# schematic_final.net
KiCad netlist of a schematic drawn in EAGLE
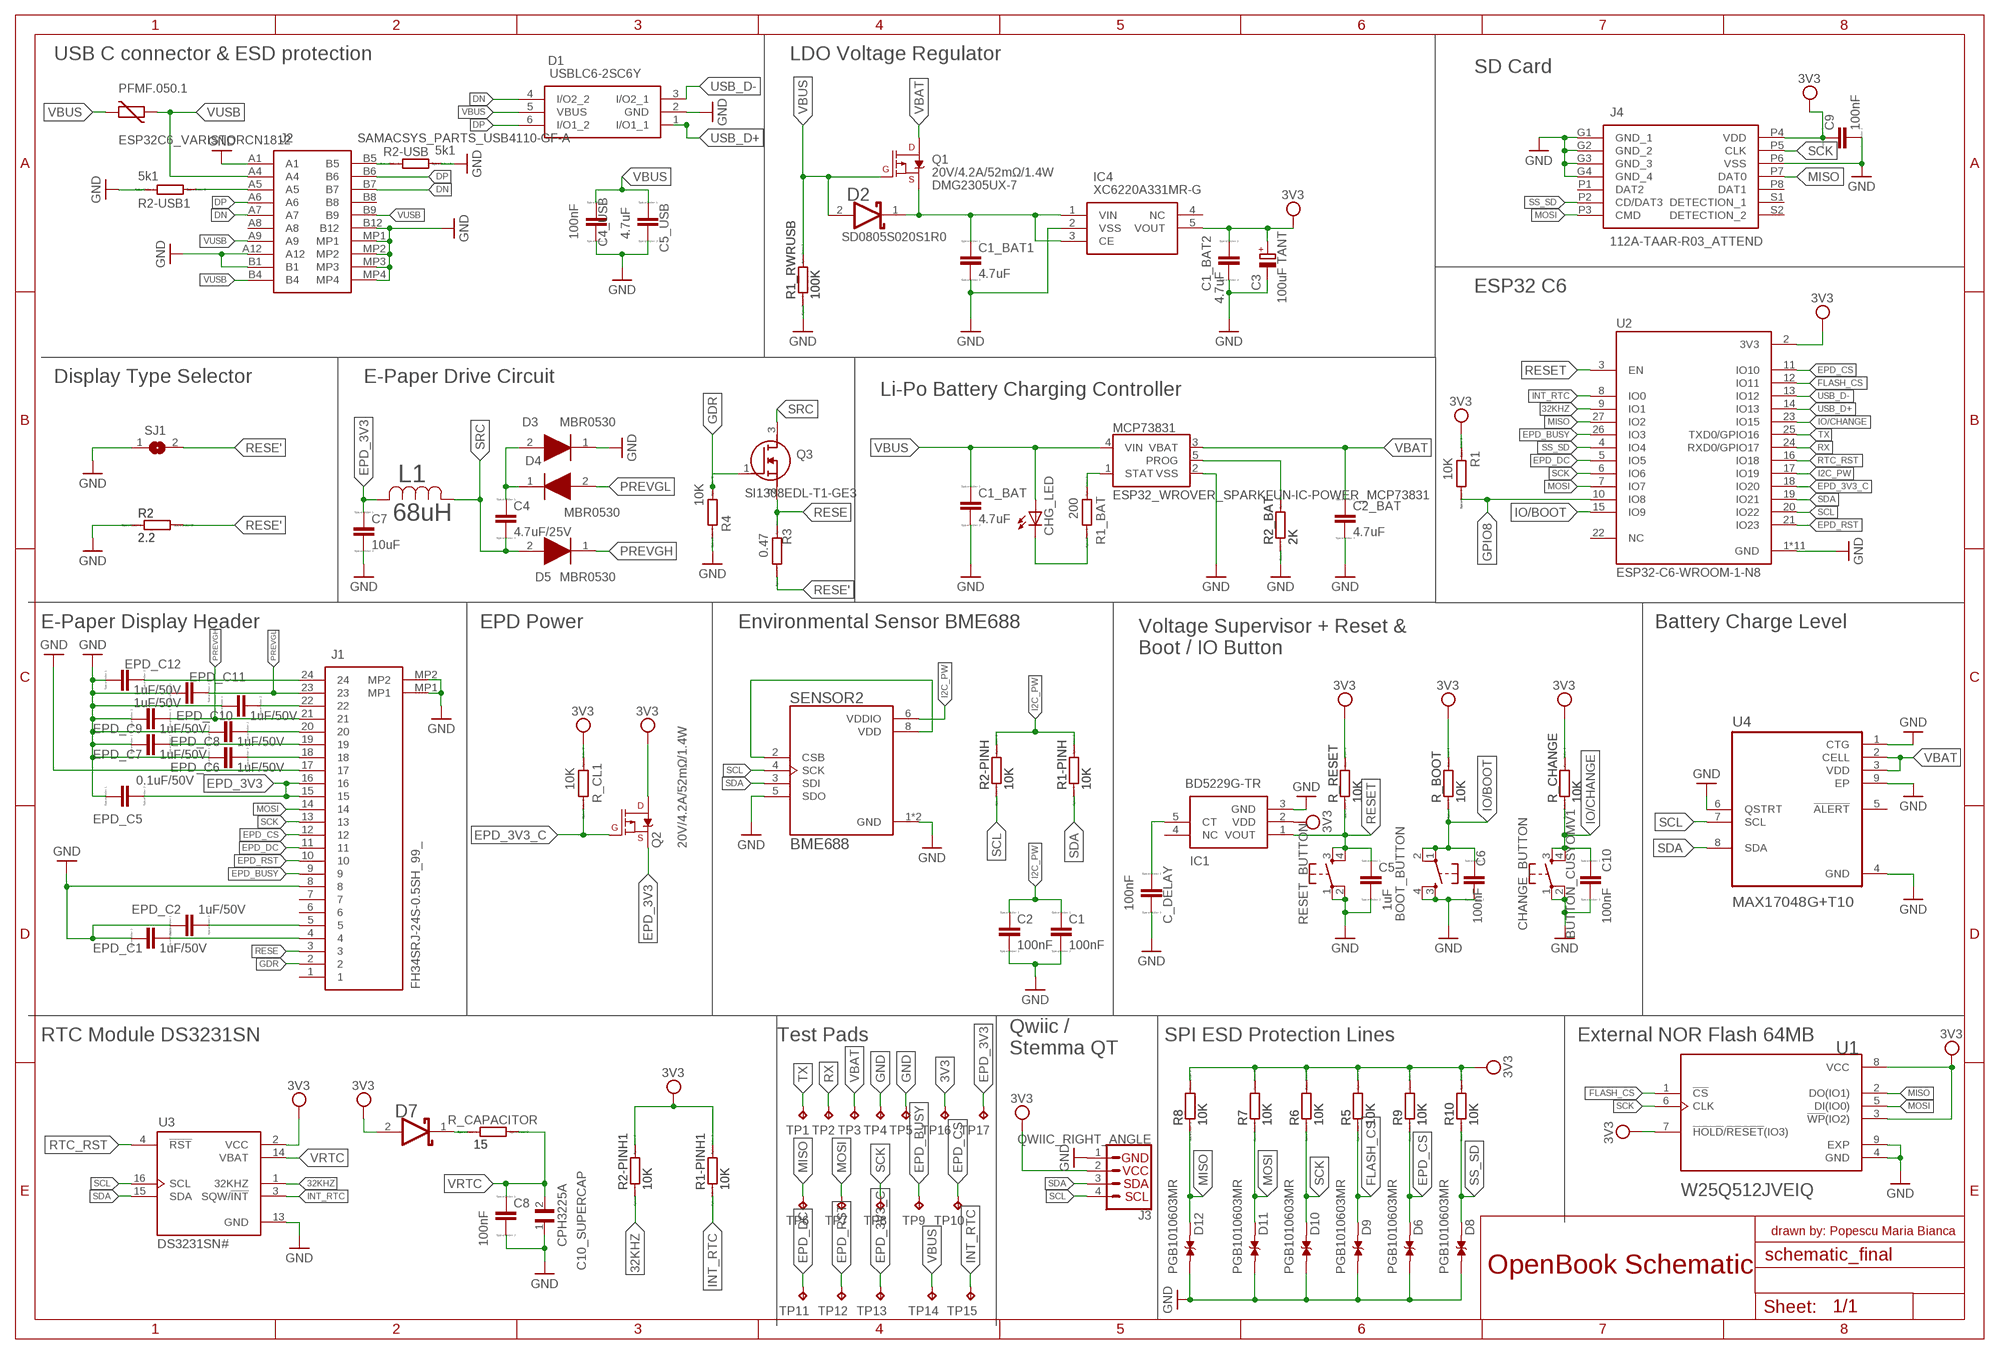
[diagram p0: schematic, sheet 1]

(export (version "E")
  (design (tool "Eeschema 10.0.6"))
  (components
    (comp (ref "BOOT_BUTTON")
      (value "BUTTON_CUSYOMV1")
      (footprint "eagle-import:MYBUTTON")
      (libsource (lib "eagle-import") (part "BUTTON_CUSYOMV1"))
    )
    (comp (ref "C1")
      (value "100nF")
      (footprint "eagle-import:EAGLE-LTSPICE_C0402")
      (libsource (lib "eagle-import") (part "EAGLE-LTSPICE_CC0402"))
    )
    (comp (ref "C1_BAT")
      (value "4.7uF")
      (footprint "eagle-import:EAGLE-LTSPICE_C0402")
      (libsource (lib "eagle-import") (part "EAGLE-LTSPICE_CC0402"))
    )
    (comp (ref "C1_BAT1")
      (value "4.7uF")
      (footprint "eagle-import:EAGLE-LTSPICE_C0402")
      (libsource (lib "eagle-import") (part "EAGLE-LTSPICE_CC0402"))
    )
    (comp (ref "C1_BAT2")
      (value "4.7uF")
      (footprint "eagle-import:EAGLE-LTSPICE_C0402")
      (libsource (lib "eagle-import") (part "EAGLE-LTSPICE_CC0402"))
    )
    (comp (ref "C2")
      (value "100nF")
      (footprint "eagle-import:EAGLE-LTSPICE_C0402")
      (libsource (lib "eagle-import") (part "EAGLE-LTSPICE_CC0402"))
    )
    (comp (ref "C2_BAT")
      (value "4.7uF")
      (footprint "eagle-import:EAGLE-LTSPICE_C0402")
      (libsource (lib "eagle-import") (part "EAGLE-LTSPICE_CC0402"))
    )
    (comp (ref "C3")
      (value "100uF TANT")
      (footprint "eagle-import:RCL_CT3528")
      (libsource (lib "eagle-import") (part "RCL_CPOL-EUCT3528"))
    )
    (comp (ref "C4")
      (value "4.7uF/25V")
      (footprint "eagle-import:EAGLE-LTSPICE_C0402")
      (libsource (lib "eagle-import") (part "EAGLE-LTSPICE_CC0402"))
    )
    (comp (ref "C4_USB")
      (value "100nF")
      (footprint "eagle-import:EAGLE-LTSPICE_C0402")
      (libsource (lib "eagle-import") (part "EAGLE-LTSPICE_CC0402"))
    )
    (comp (ref "C5")
      (value "1uF")
      (footprint "eagle-import:EAGLE-LTSPICE_C0402")
      (libsource (lib "eagle-import") (part "EAGLE-LTSPICE_CC0402"))
    )
    (comp (ref "C5_USB")
      (value "4.7uF")
      (footprint "eagle-import:EAGLE-LTSPICE_C0402")
      (libsource (lib "eagle-import") (part "EAGLE-LTSPICE_CC0402"))
    )
    (comp (ref "C6")
      (value "100nF")
      (footprint "eagle-import:EAGLE-LTSPICE_C0402")
      (libsource (lib "eagle-import") (part "EAGLE-LTSPICE_CC0402"))
    )
    (comp (ref "C7")
      (value "10uF")
      (footprint "eagle-import:EAGLE-LTSPICE_C0402")
      (libsource (lib "eagle-import") (part "EAGLE-LTSPICE_CC0402"))
    )
    (comp (ref "C8")
      (value "100nF")
      (footprint "eagle-import:EAGLE-LTSPICE_C0402")
      (libsource (lib "eagle-import") (part "EAGLE-LTSPICE_CC0402"))
    )
    (comp (ref "C9")
      (value "100nF")
      (footprint "eagle-import:EAGLE-LTSPICE_C0402")
      (libsource (lib "eagle-import") (part "EAGLE-LTSPICE_CC0402"))
    )
    (comp (ref "C10")
      (value "100nF")
      (footprint "eagle-import:EAGLE-LTSPICE_C0402")
      (libsource (lib "eagle-import") (part "EAGLE-LTSPICE_CC0402"))
    )
    (comp (ref "C10_SUPERCAP")
      (value "CPH3225A")
      (footprint "eagle-import:CAPCP3225X100N")
      (fields (field (name "MF") "Seiko Instruments"))
      (libsource (lib "eagle-import") (part "CPH3225A"))
    )
    (comp (ref "CHANGE_BUTTON")
      (value "BUTTON_CUSYOMV1")
      (footprint "eagle-import:MYBUTTON")
      (libsource (lib "eagle-import") (part "BUTTON_CUSYOMV1"))
    )
    (comp (ref "CHG_LED")
      (value "ADAFRUIT_LEDCHIP-LED0603")
      (footprint "eagle-import:ADAFRUIT_CHIP-LED0603")
      (libsource (lib "eagle-import") (part "ADAFRUIT_LEDCHIP-LED0603"))
    )
    (comp (ref "C_DELAY")
      (value "100nF")
      (footprint "eagle-import:EAGLE-LTSPICE_C0402")
      (libsource (lib "eagle-import") (part "EAGLE-LTSPICE_CC0402"))
    )
    (comp (ref "D1")
      (value "USBLC6-2SC6Y")
      (footprint "eagle-import:SOT95P280X145-6N")
      (fields (field (name "MF") "STMicroelectronics"))
      (libsource (lib "eagle-import") (part "USBLC6-2SC6Y"))
    )
    (comp (ref "D2")
      (value "SD0805S020S1R0")
      (footprint "eagle-import:ESP32_WROVER_AVX---SD0805S020S1R0_AVX_SD0805S020S1R0_0")
      (fields
        (field (name "DIGIKEY_PART_NUMBER") "478-7800-1-ND")
        (field (name "MF") "AVX")
        (field (name "MOUSER_PART_NUMBER") "581-SD0805S020S1R0")
        (field (name "ATTR") "SD0805S020S1R0")
      )
      (libsource (lib "eagle-import") (part "ESP32_WROVER_AVX---SD0805S020S1R0_AVX_SD0805S020S1R0_0_0AVX_SD0805S020S1R0_0_0"))
    )
    (comp (ref "D3")
      (value "MBR0530")
      (footprint "eagle-import:SOD3716X135N")
      (fields (field (name "MF") "ON Semiconductor"))
      (libsource (lib "eagle-import") (part "MBR0530"))
    )
    (comp (ref "D4")
      (value "MBR0530")
      (footprint "eagle-import:SOD3716X135N")
      (fields (field (name "MF") "ON Semiconductor"))
      (libsource (lib "eagle-import") (part "MBR0530"))
    )
    (comp (ref "D5")
      (value "MBR0530")
      (footprint "eagle-import:SOD3716X135N")
      (fields (field (name "MF") "ON Semiconductor"))
      (libsource (lib "eagle-import") (part "MBR0530"))
    )
    (comp (ref "D6")
      (value "PGB1010603MR")
      (footprint "eagle-import:DIOC1608X36N")
      (fields (field (name "MF") "Littelfuse Inc."))
      (libsource (lib "eagle-import") (part "PGB1010603MR"))
    )
    (comp (ref "D7")
      (value "ESP32_WROVER_AVX---SD0805S020S1R0_AVX_SD0805S020S1R0_0_0AVX_SD0805S020S1R0_0_0")
      (footprint "eagle-import:ESP32_WROVER_AVX---SD0805S020S1R0_AVX_SD0805S020S1R0_0")
      (fields
        (field (name "DIGIKEY_PART_NUMBER") "478-7800-1-ND")
        (field (name "MF") "AVX")
        (field (name "MOUSER_PART_NUMBER") "581-SD0805S020S1R0")
      )
      (libsource (lib "eagle-import") (part "ESP32_WROVER_AVX---SD0805S020S1R0_AVX_SD0805S020S1R0_0_0AVX_SD0805S020S1R0_0_0"))
    )
    (comp (ref "D8")
      (value "PGB1010603MR")
      (footprint "eagle-import:DIOC1608X36N")
      (fields (field (name "MF") "Littelfuse Inc."))
      (libsource (lib "eagle-import") (part "PGB1010603MR"))
    )
    (comp (ref "D9")
      (value "PGB1010603MR")
      (footprint "eagle-import:DIOC1608X36N")
      (fields (field (name "MF") "Littelfuse Inc."))
      (libsource (lib "eagle-import") (part "PGB1010603MR"))
    )
    (comp (ref "D10")
      (value "PGB1010603MR")
      (footprint "eagle-import:DIOC1608X36N")
      (fields (field (name "MF") "Littelfuse Inc."))
      (libsource (lib "eagle-import") (part "PGB1010603MR"))
    )
    (comp (ref "D11")
      (value "PGB1010603MR")
      (footprint "eagle-import:DIOC1608X36N")
      (fields (field (name "MF") "Littelfuse Inc."))
      (libsource (lib "eagle-import") (part "PGB1010603MR"))
    )
    (comp (ref "D12")
      (value "PGB1010603MR")
      (footprint "eagle-import:DIOC1608X36N")
      (fields (field (name "MF") "Littelfuse Inc."))
      (libsource (lib "eagle-import") (part "PGB1010603MR"))
    )
    (comp (ref "EPD_C1")
      (value "1uF/50V")
      (footprint "eagle-import:EAGLE-LTSPICE_C0402")
      (libsource (lib "eagle-import") (part "EAGLE-LTSPICE_CC0402"))
    )
    (comp (ref "EPD_C2")
      (value "1uF/50V")
      (footprint "eagle-import:EAGLE-LTSPICE_C0402")
      (libsource (lib "eagle-import") (part "EAGLE-LTSPICE_CC0402"))
    )
    (comp (ref "EPD_C5")
      (value "0.1uF/50V")
      (footprint "eagle-import:EAGLE-LTSPICE_C0402")
      (libsource (lib "eagle-import") (part "EAGLE-LTSPICE_CC0402"))
    )
    (comp (ref "EPD_C6")
      (value "1uF/50V")
      (footprint "eagle-import:EAGLE-LTSPICE_C0402")
      (libsource (lib "eagle-import") (part "EAGLE-LTSPICE_CC0402"))
    )
    (comp (ref "EPD_C7")
      (value "1uF/50V")
      (footprint "eagle-import:EAGLE-LTSPICE_C0402")
      (libsource (lib "eagle-import") (part "EAGLE-LTSPICE_CC0402"))
    )
    (comp (ref "EPD_C8")
      (value "1uF/50V")
      (footprint "eagle-import:EAGLE-LTSPICE_C0402")
      (libsource (lib "eagle-import") (part "EAGLE-LTSPICE_CC0402"))
    )
    (comp (ref "EPD_C9")
      (value "1uF/50V")
      (footprint "eagle-import:EAGLE-LTSPICE_C0402")
      (libsource (lib "eagle-import") (part "EAGLE-LTSPICE_CC0402"))
    )
    (comp (ref "EPD_C10")
      (value "1uF/50V")
      (footprint "eagle-import:EAGLE-LTSPICE_C0402")
      (libsource (lib "eagle-import") (part "EAGLE-LTSPICE_CC0402"))
    )
    (comp (ref "EPD_C11")
      (value "1uF/50V")
      (footprint "eagle-import:EAGLE-LTSPICE_C0402")
      (libsource (lib "eagle-import") (part "EAGLE-LTSPICE_CC0402"))
    )
    (comp (ref "EPD_C12")
      (value "1uF/50V")
      (footprint "eagle-import:EAGLE-LTSPICE_C0402")
      (libsource (lib "eagle-import") (part "EAGLE-LTSPICE_CC0402"))
    )
    (comp (ref "IC1")
      (value "BD5229G-TR")
      (footprint "eagle-import:SOT95P280X125-5N")
      (fields (field (name "MOUSER_PART_NUMBER") "755-BD5229G-TR"))
      (libsource (lib "eagle-import") (part "BD5229G-TR"))
    )
    (comp (ref "IC4")
      (value "XC6220A331MR-G")
      (footprint "eagle-import:SOT95P280X120-5N")
      (fields (field (name "MOUSER_PART_NUMBER") "865-XC6220A331MR-G"))
      (libsource (lib "eagle-import") (part "XC6220A331MR-G"))
    )
    (comp (ref "J1")
      (value "FH34SRJ-24S-0.5SH_99_")
      (footprint "eagle-import:FH34SRJ24S05SH99")
      (fields
        (field (name "MANUFACTURER_PART_NUMBER") "FH34SRJ-24S-0.5SH(99)")
        (field (name "MOUSER_PART_NUMBER") "798-FH34SRJ24S05SH99")
      )
      (libsource (lib "eagle-import") (part "FH34SRJ-24S-0.5SH_99_"))
    )
    (comp (ref "J2")
      (value "SAMACSYS_PARTS_USB4110-GF-A")
      (footprint "eagle-import:SAMACSYS_PARTS_USB4110GFA")
      (fields
        (field (name "MANUFACTURER_PART_NUMBER") "USB4110-GF-A")
        (field (name "MOUSER_PART_NUMBER") "640-USB4110-GF-A")
      )
      (libsource (lib "eagle-import") (part "SAMACSYS_PARTS_USB4110-GF-A"))
    )
    (comp (ref "J3")
      (value "QWIIC_RIGHT_ANGLE")
      (footprint "eagle-import:JST04_1MM_RA")
      (libsource (lib "eagle-import") (part "QWIIC_CONNECTORJS-1MM"))
    )
    (comp (ref "J4")
      (value "112A-TAAR-R03_ATTEND")
      (footprint "eagle-import:112ATAARR03ATTEND")
      (fields (field (name "MANUFACTURER_PART_NUMBER") "112A-TAAR-R03 ATTEND"))
      (libsource (lib "eagle-import") (part "112A-TAAR-R03_ATTEND"))
    )
    (comp (ref "L1")
      (value "68uH")
      (footprint "eagle-import:IND_4828-WE-TPC_WRE")
      (fields
        (field (name "MANUFACTURER_PART_NUMBER") "744043680")
        (field (name "COPYRIGHT") "Copyright (C) 2024 Ultra Librarian. All rights reserved.")
      )
      (libsource (lib "eagle-import") (part "744043680IND_4828-WE-TPC_WRE"))
    )
    (comp (ref "MCP73831")
      (value "ESP32_WROVER_SPARKFUN-IC-POWER_MCP73831")
      (footprint "eagle-import:ESP32_WROVER_SPARKFUN-IC-POWER_SOT23-5")
      (libsource (lib "eagle-import") (part "ESP32_WROVER_SPARKFUN-IC-POWER_MCP73831"))
    )
    (comp (ref "PFMF.050.1")
      (value "ESP32C6_VARISTORCN1812")
      (footprint "eagle-import:ESP32C6_VARISTOR_CT_CN1812")
      (libsource (lib "eagle-import") (part "ESP32C6_VARISTORCN1812"))
    )
    (comp (ref "Q1")
      (value "20V/4.2A/52mΩ/1.4W")
      (footprint "eagle-import:ESP32_WROVER_SPARKFUN-DISCRETESEMI_SOT23-3")
      (fields (field (name "ATTR") "DMG2305UX-7"))
      (libsource (lib "eagle-import") (part "ESP32_WROVER_SPARKFUN-DISCRETESEMI_MOSFET_PCH-DMG2305UX-7"))
    )
    (comp (ref "Q2")
      (value "20V/4.2A/52mΩ/1.4W")
      (footprint "eagle-import:ESP32_WROVER_SPARKFUN-DISCRETESEMI_SOT23-3")
      (libsource (lib "eagle-import") (part "ESP32_WROVER_SPARKFUN-DISCRETESEMI_MOSFET_PCH-DMG2305UX-7"))
    )
    (comp (ref "Q3")
      (value "SI1308EDL-T1-GE3")
      (footprint "eagle-import:SOT65P210X110-3N")
      (fields (field (name "MF") "Vishay Siliconix"))
      (libsource (lib "eagle-import") (part "SI1308EDL-T1-GE3"))
    )
    (comp (ref "R1")
      (value "10K")
      (footprint "eagle-import:ESP32_WROVER_EAGLE-LTSPICE_R0402")
      (libsource (lib "eagle-import") (part "ESP32_WROVER_EAGLE-LTSPICE_RR0402"))
    )
    (comp (ref "R1-PINH")
      (value "10K")
      (footprint "eagle-import:ESP32_WROVER_EAGLE-LTSPICE_R0402")
      (libsource (lib "eagle-import") (part "ESP32_WROVER_EAGLE-LTSPICE_RR0402"))
    )
    (comp (ref "R1-PINH1")
      (value "10K")
      (footprint "eagle-import:ESP32_WROVER_EAGLE-LTSPICE_R0402")
      (libsource (lib "eagle-import") (part "ESP32_WROVER_EAGLE-LTSPICE_RR0402"))
    )
    (comp (ref "R1_BAT")
      (value "200")
      (footprint "eagle-import:ESP32_WROVER_EAGLE-LTSPICE_R0402")
      (libsource (lib "eagle-import") (part "ESP32_WROVER_EAGLE-LTSPICE_RR0402"))
    )
    (comp (ref "R1_RWRUSB")
      (value "100K")
      (footprint "eagle-import:ESP32_WROVER_EAGLE-LTSPICE_R0402")
      (libsource (lib "eagle-import") (part "ESP32_WROVER_EAGLE-LTSPICE_RR0402"))
    )
    (comp (ref "R2")
      (value "2.2")
      (footprint "eagle-import:ESP32_WROVER_EAGLE-LTSPICE_R0402")
      (libsource (lib "eagle-import") (part "ESP32_WROVER_EAGLE-LTSPICE_RR0402"))
    )
    (comp (ref "R2-PINH")
      (value "10K")
      (footprint "eagle-import:ESP32_WROVER_EAGLE-LTSPICE_R0402")
      (libsource (lib "eagle-import") (part "ESP32_WROVER_EAGLE-LTSPICE_RR0402"))
    )
    (comp (ref "R2-PINH1")
      (value "10K")
      (footprint "eagle-import:ESP32_WROVER_EAGLE-LTSPICE_R0402")
      (libsource (lib "eagle-import") (part "ESP32_WROVER_EAGLE-LTSPICE_RR0402"))
    )
    (comp (ref "R2-USB")
      (value "5k1")
      (footprint "eagle-import:ESP32_WROVER_EAGLE-LTSPICE_R0402")
      (libsource (lib "eagle-import") (part "ESP32_WROVER_EAGLE-LTSPICE_RR0402"))
    )
    (comp (ref "R2-USB1")
      (value "5k1")
      (footprint "eagle-import:ESP32_WROVER_EAGLE-LTSPICE_R0402")
      (libsource (lib "eagle-import") (part "ESP32_WROVER_EAGLE-LTSPICE_RR0402"))
    )
    (comp (ref "R2_BAT")
      (value "2K")
      (footprint "eagle-import:ESP32_WROVER_EAGLE-LTSPICE_R0402")
      (libsource (lib "eagle-import") (part "ESP32_WROVER_EAGLE-LTSPICE_RR0402"))
    )
    (comp (ref "R3")
      (value "0.47")
      (footprint "eagle-import:ESP32_WROVER_EAGLE-LTSPICE_R0402")
      (libsource (lib "eagle-import") (part "ESP32_WROVER_EAGLE-LTSPICE_RR0402"))
    )
    (comp (ref "R4")
      (value "10K")
      (footprint "eagle-import:ESP32_WROVER_EAGLE-LTSPICE_R0402")
      (libsource (lib "eagle-import") (part "ESP32_WROVER_EAGLE-LTSPICE_RR0402"))
    )
    (comp (ref "R5")
      (value "10K")
      (footprint "eagle-import:ESP32_WROVER_EAGLE-LTSPICE_R0402")
      (libsource (lib "eagle-import") (part "ESP32_WROVER_EAGLE-LTSPICE_RR0402"))
    )
    (comp (ref "R6")
      (value "10K")
      (footprint "eagle-import:ESP32_WROVER_EAGLE-LTSPICE_R0402")
      (libsource (lib "eagle-import") (part "ESP32_WROVER_EAGLE-LTSPICE_RR0402"))
    )
    (comp (ref "R7")
      (value "10K")
      (footprint "eagle-import:ESP32_WROVER_EAGLE-LTSPICE_R0402")
      (libsource (lib "eagle-import") (part "ESP32_WROVER_EAGLE-LTSPICE_RR0402"))
    )
    (comp (ref "R8")
      (value "10K")
      (footprint "eagle-import:ESP32_WROVER_EAGLE-LTSPICE_R0402")
      (libsource (lib "eagle-import") (part "ESP32_WROVER_EAGLE-LTSPICE_RR0402"))
    )
    (comp (ref "R9")
      (value "10K")
      (footprint "eagle-import:ESP32_WROVER_EAGLE-LTSPICE_R0402")
      (libsource (lib "eagle-import") (part "ESP32_WROVER_EAGLE-LTSPICE_RR0402"))
    )
    (comp (ref "R10")
      (value "10K")
      (footprint "eagle-import:ESP32_WROVER_EAGLE-LTSPICE_R0402")
      (libsource (lib "eagle-import") (part "ESP32_WROVER_EAGLE-LTSPICE_RR0402"))
    )
    (comp (ref "RESET_BUTTON")
      (value "RESET_BUTTON")
      (footprint "eagle-import:MYBUTTON")
      (libsource (lib "eagle-import") (part "BUTTON_CUSYOMV1"))
    )
    (comp (ref "R_BOOT")
      (value "10K")
      (footprint "eagle-import:ESP32_WROVER_EAGLE-LTSPICE_R0402")
      (libsource (lib "eagle-import") (part "ESP32_WROVER_EAGLE-LTSPICE_RR0402"))
    )
    (comp (ref "R_CAPACITOR")
      (value "15")
      (footprint "eagle-import:ESP32_WROVER_EAGLE-LTSPICE_R0402")
      (libsource (lib "eagle-import") (part "ESP32_WROVER_EAGLE-LTSPICE_RR0402"))
    )
    (comp (ref "R_CHANGE")
      (value "10K")
      (footprint "eagle-import:ESP32_WROVER_EAGLE-LTSPICE_R0402")
      (libsource (lib "eagle-import") (part "ESP32_WROVER_EAGLE-LTSPICE_RR0402"))
    )
    (comp (ref "R_CL1")
      (value "10K")
      (footprint "eagle-import:ESP32_WROVER_EAGLE-LTSPICE_R0402")
      (libsource (lib "eagle-import") (part "ESP32_WROVER_EAGLE-LTSPICE_RR0402"))
    )
    (comp (ref "R_RESET")
      (value "10K")
      (footprint "eagle-import:ESP32_WROVER_EAGLE-LTSPICE_R0402")
      (libsource (lib "eagle-import") (part "ESP32_WROVER_EAGLE-LTSPICE_RR0402"))
    )
    (comp (ref "SENSOR2")
      (value "BME688")
      (footprint "eagle-import:ESP32_WROVER_BME680_PSON80P300X300X100-8N")
      (fields (field (name "MF") "Bosch Sensortec") (field (name "MP") "BME680"))
      (libsource (lib "eagle-import") (part "ESP32_WROVER_BME680_BME680"))
    )
    (comp (ref "SJ1") (value "SJ") (footprint "eagle-import:SJ") (libsource (lib "eagle-import") (part "SJ")))
    (comp (ref "TP1")
      (value "TPTP20R")
      (footprint "eagle-import:TP20R")
      (libsource (lib "eagle-import") (part "TPTP20R"))
    )
    (comp (ref "TP2")
      (value "TPTP20R")
      (footprint "eagle-import:TP20R")
      (libsource (lib "eagle-import") (part "TPTP20R"))
    )
    (comp (ref "TP3")
      (value "TPTP20R")
      (footprint "eagle-import:TP20R")
      (libsource (lib "eagle-import") (part "TPTP20R"))
    )
    (comp (ref "TP4")
      (value "TPTP20R")
      (footprint "eagle-import:TP20R")
      (libsource (lib "eagle-import") (part "TPTP20R"))
    )
    (comp (ref "TP5")
      (value "TPTP20R")
      (footprint "eagle-import:TP20R")
      (libsource (lib "eagle-import") (part "TPTP20R"))
    )
    (comp (ref "TP6")
      (value "TPTP20R")
      (footprint "eagle-import:TP20R")
      (libsource (lib "eagle-import") (part "TPTP20R"))
    )
    (comp (ref "TP7")
      (value "TPTP20R")
      (footprint "eagle-import:TP20R")
      (libsource (lib "eagle-import") (part "TPTP20R"))
    )
    (comp (ref "TP8")
      (value "TPTP20R")
      (footprint "eagle-import:TP20R")
      (libsource (lib "eagle-import") (part "TPTP20R"))
    )
    (comp (ref "TP9")
      (value "TPTP20R")
      (footprint "eagle-import:TP20R")
      (libsource (lib "eagle-import") (part "TPTP20R"))
    )
    (comp (ref "TP10")
      (value "TPTP20R")
      (footprint "eagle-import:TP20R")
      (libsource (lib "eagle-import") (part "TPTP20R"))
    )
    (comp (ref "TP11")
      (value "TPTP20R")
      (footprint "eagle-import:TP20R")
      (libsource (lib "eagle-import") (part "TPTP20R"))
    )
    (comp (ref "TP12")
      (value "TPTP20R")
      (footprint "eagle-import:TP20R")
      (libsource (lib "eagle-import") (part "TPTP20R"))
    )
    (comp (ref "TP13")
      (value "TPTP20R")
      (footprint "eagle-import:TP20R")
      (libsource (lib "eagle-import") (part "TPTP20R"))
    )
    (comp (ref "TP14")
      (value "TPTP20R")
      (footprint "eagle-import:TP20R")
      (libsource (lib "eagle-import") (part "TPTP20R"))
    )
    (comp (ref "TP15")
      (value "TPTP20R")
      (footprint "eagle-import:TP20R")
      (libsource (lib "eagle-import") (part "TPTP20R"))
    )
    (comp (ref "TP16")
      (value "TPTP20R")
      (footprint "eagle-import:TP20R")
      (libsource (lib "eagle-import") (part "TPTP20R"))
    )
    (comp (ref "TP17")
      (value "TPTP20R")
      (footprint "eagle-import:TP20R")
      (libsource (lib "eagle-import") (part "TPTP20R"))
    )
    (comp (ref "U1")
      (value "W25Q512JVEIQ")
      (footprint "eagle-import:SON127P600X800X80-9N")
      (fields (field (name "MF") "Winbond Electronics"))
      (libsource (lib "eagle-import") (part "W25Q512JVEIQ"))
    )
    (comp (ref "U2")
      (value "ESP32-C6-WROOM-1-N8")
      (footprint "eagle-import:XCVR_ESP32-C6-WROOM-1-N8")
      (fields (field (name "MF") "Espressif Systems"))
      (libsource (lib "eagle-import") (part "ESP32-C6-WROOM-1-N8"))
    )
    (comp (ref "U3")
      (value "DS3231SN#")
      (footprint "eagle-import:SOIC127P1032X265-16N")
      (fields (field (name "MF") "Analog Devices"))
      (libsource (lib "eagle-import") (part "DS3231SN#"))
    )
    (comp (ref "U4")
      (value "MAX17048G+T10")
      (footprint "eagle-import:SON50P200X200X80-9N")
      (fields (field (name "MF") "Analog Devices"))
      (libsource (lib "eagle-import") (part "MAX17048G+T10"))
    )
  )
  (nets
    (net (code "1") (name "3V3") (class "Default")
      (node (ref "C1_BAT2") (pin "1") (pinfunction "1_1") (pintype "passive"))
      (node (ref "C3") (pin "+") (pinfunction "+_+") (pintype "passive"))
      (node (ref "C9") (pin "1") (pinfunction "1_1") (pintype "passive"))
      (node (ref "D7") (pin "2") (pinfunction "ANODE_2") (pintype "bidirectional"))
      (node (ref "IC1") (pin "2") (pinfunction "VDD_2") (pintype "bidirectional"))
      (node (ref "IC4") (pin "5") (pinfunction "VOUT_5") (pintype "bidirectional"))
      (node (ref "J3") (pin "2") (pinfunction "2_2") (pintype "power_in"))
      (node (ref "J4") (pin "P4") (pinfunction "VDD_P4") (pintype "bidirectional"))
      (node (ref "Q2") (pin "3") (pinfunction "D_3") (pintype "bidirectional"))
      (node (ref "R1") (pin "2") (pinfunction "2_2") (pintype "passive"))
      (node (ref "R1-PINH1") (pin "2") (pinfunction "2_2") (pintype "passive"))
      (node (ref "R10") (pin "2") (pinfunction "2_2") (pintype "passive"))
      (node (ref "R2-PINH1") (pin "2") (pinfunction "2_2") (pintype "passive"))
      (node (ref "R5") (pin "2") (pinfunction "2_2") (pintype "passive"))
      (node (ref "R6") (pin "2") (pinfunction "2_2") (pintype "passive"))
      (node (ref "R7") (pin "2") (pinfunction "2_2") (pintype "passive"))
      (node (ref "R8") (pin "2") (pinfunction "2_2") (pintype "passive"))
      (node (ref "R9") (pin "2") (pinfunction "2_2") (pintype "passive"))
      (node (ref "R_BOOT") (pin "2") (pinfunction "2_2") (pintype "passive"))
      (node (ref "R_CHANGE") (pin "2") (pinfunction "2_2") (pintype "passive"))
      (node (ref "R_CL1") (pin "2") (pinfunction "2_2") (pintype "passive"))
      (node (ref "R_RESET") (pin "2") (pinfunction "2_2") (pintype "passive"))
      (node (ref "TP16") (pin "TP") (pinfunction "TP_TP") (pintype "input"))
      (node (ref "U1") (pin "3") (pinfunction "~{WP}(IO2)_3") (pintype "bidirectional"))
      (node (ref "U1") (pin "7") (pinfunction "~{HOLD}/~{RESET}(IO3)_7") (pintype "bidirectional"))
      (node (ref "U1") (pin "8") (pinfunction "VCC_8") (pintype "power_in"))
      (node (ref "U2") (pin "2") (pinfunction "3V3_2") (pintype "power_in"))
      (node (ref "U3") (pin "2") (pinfunction "VCC_2") (pintype "power_in"))
    )
    (net (code "2") (name "32KHZ") (class "Default")
      (node (ref "R2-PINH1") (pin "1") (pinfunction "1_1") (pintype "passive"))
      (node (ref "U2") (pin "9") (pinfunction "IO1_9") (pintype "bidirectional"))
      (node (ref "U3") (pin "1") (pinfunction "32KHZ_1") (pintype "output"))
    )
    (net (code "3") (name "DN") (class "Default")
      (node (ref "D1") (pin "4") (pinfunction "I/O2_2_4") (pintype "bidirectional"))
      (node (ref "J2") (pin "A7") (pinfunction "A7_A7") (pintype "bidirectional"))
      (node (ref "J2") (pin "B7") (pinfunction "B7_B7") (pintype "bidirectional"))
    )
    (net (code "4") (name "DP") (class "Default")
      (node (ref "D1") (pin "6") (pinfunction "I/O1_2_6") (pintype "bidirectional"))
      (node (ref "J2") (pin "A6") (pinfunction "A6_A6") (pintype "bidirectional"))
      (node (ref "J2") (pin "B6") (pinfunction "B6_B6") (pintype "bidirectional"))
    )
    (net (code "5") (name "EPD_3V3") (class "Default")
      (node (ref "C7") (pin "1") (pinfunction "1_1") (pintype "passive"))
      (node (ref "EPD_C5") (pin "2") (pinfunction "2_2") (pintype "passive"))
      (node (ref "J1") (pin "15") (pinfunction "15_15") (pintype "bidirectional"))
      (node (ref "J1") (pin "16") (pinfunction "16_16") (pintype "bidirectional"))
      (node (ref "L1") (pin "2") (pinfunction "2_2") (pintype "passive"))
      (node (ref "Q2") (pin "2") (pinfunction "S_2") (pintype "bidirectional"))
      (node (ref "TP17") (pin "TP") (pinfunction "TP_TP") (pintype "input"))
    )
    (net (code "6") (name "EPD_3V3_C") (class "Default")
      (node (ref "Q2") (pin "1") (pinfunction "G_1") (pintype "bidirectional"))
      (node (ref "R_CL1") (pin "1") (pinfunction "1_1") (pintype "passive"))
      (node (ref "TP13") (pin "TP") (pinfunction "TP_TP") (pintype "input"))
      (node (ref "U2") (pin "18") (pinfunction "IO20_18") (pintype "bidirectional"))
    )
    (net (code "7") (name "EPD_BUSY") (class "Default")
      (node (ref "J1") (pin "9") (pinfunction "9_9") (pintype "bidirectional"))
      (node (ref "TP9") (pin "TP") (pinfunction "TP_TP") (pintype "input"))
      (node (ref "U2") (pin "26") (pinfunction "IO3_26") (pintype "bidirectional"))
    )
    (net (code "8") (name "EPD_CS") (class "Default")
      (node (ref "D6") (pin "2") (pinfunction "2_2") (pintype "passive"))
      (node (ref "J1") (pin "12") (pinfunction "12_12") (pintype "bidirectional"))
      (node (ref "R9") (pin "1") (pinfunction "1_1") (pintype "passive"))
      (node (ref "TP10") (pin "TP") (pinfunction "TP_TP") (pintype "input"))
      (node (ref "U2") (pin "11") (pinfunction "IO10_11") (pintype "bidirectional"))
    )
    (net (code "9") (name "EPD_DC") (class "Default")
      (node (ref "J1") (pin "11") (pinfunction "11_11") (pintype "bidirectional"))
      (node (ref "TP11") (pin "TP") (pinfunction "TP_TP") (pintype "input"))
      (node (ref "U2") (pin "5") (pinfunction "IO5_5") (pintype "bidirectional"))
    )
    (net (code "10") (name "EPD_RST") (class "Default")
      (node (ref "J1") (pin "10") (pinfunction "10_10") (pintype "bidirectional"))
      (node (ref "TP12") (pin "TP") (pinfunction "TP_TP") (pintype "input"))
      (node (ref "U2") (pin "21") (pinfunction "IO23_21") (pintype "bidirectional"))
    )
    (net (code "11") (name "FLASH_CS") (class "Default")
      (node (ref "D9") (pin "2") (pinfunction "2_2") (pintype "passive"))
      (node (ref "R5") (pin "1") (pinfunction "1_1") (pintype "passive"))
      (node (ref "U1") (pin "1") (pinfunction "~{CS}_1") (pintype "input"))
      (node (ref "U2") (pin "12") (pinfunction "IO11_12") (pintype "bidirectional"))
    )
    (net (code "12") (name "GDR") (class "Default")
      (node (ref "J1") (pin "2") (pinfunction "2_2") (pintype "bidirectional"))
      (node (ref "Q3") (pin "1") (pinfunction "G_1") (pintype "bidirectional"))
      (node (ref "R4") (pin "2") (pinfunction "2_2") (pintype "passive"))
    )
    (net (code "13") (name "GND") (class "Default")
      (node (ref "BOOT_BUTTON") (pin "3") (pinfunction "3_3") (pintype "passive"))
      (node (ref "BOOT_BUTTON") (pin "4") (pinfunction "4_4") (pintype "passive"))
      (node (ref "C1") (pin "2") (pinfunction "2_2") (pintype "passive"))
      (node (ref "C10") (pin "2") (pinfunction "2_2") (pintype "passive"))
      (node (ref "C10_SUPERCAP") (pin "1") (pinfunction "1_1") (pintype "passive"))
      (node (ref "C1_BAT") (pin "2") (pinfunction "2_2") (pintype "passive"))
      (node (ref "C1_BAT1") (pin "2") (pinfunction "2_2") (pintype "passive"))
      (node (ref "C1_BAT2") (pin "2") (pinfunction "2_2") (pintype "passive"))
      (node (ref "C2") (pin "2") (pinfunction "2_2") (pintype "passive"))
      (node (ref "C2_BAT") (pin "2") (pinfunction "2_2") (pintype "passive"))
      (node (ref "C3") (pin "-") (pinfunction "-_-") (pintype "passive"))
      (node (ref "C4_USB") (pin "2") (pinfunction "2_2") (pintype "passive"))
      (node (ref "C5") (pin "2") (pinfunction "2_2") (pintype "passive"))
      (node (ref "C5_USB") (pin "2") (pinfunction "2_2") (pintype "passive"))
      (node (ref "C6") (pin "2") (pinfunction "2_2") (pintype "passive"))
      (node (ref "C7") (pin "2") (pinfunction "2_2") (pintype "passive"))
      (node (ref "C8") (pin "2") (pinfunction "2_2") (pintype "passive"))
      (node (ref "C9") (pin "2") (pinfunction "2_2") (pintype "passive"))
      (node (ref "CHANGE_BUTTON") (pin "1") (pinfunction "1_1") (pintype "passive"))
      (node (ref "CHANGE_BUTTON") (pin "2") (pinfunction "2_2") (pintype "passive"))
      (node (ref "C_DELAY") (pin "2") (pinfunction "2_2") (pintype "passive"))
      (node (ref "D1") (pin "2") (pinfunction "GND_2") (pintype "bidirectional"))
      (node (ref "D10") (pin "1") (pinfunction "1_1") (pintype "passive"))
      (node (ref "D11") (pin "1") (pinfunction "1_1") (pintype "passive"))
      (node (ref "D12") (pin "1") (pinfunction "1_1") (pintype "passive"))
      (node (ref "D3") (pin "1") (pinfunction "K_1") (pintype "bidirectional"))
      (node (ref "D6") (pin "1") (pinfunction "1_1") (pintype "passive"))
      (node (ref "D8") (pin "1") (pinfunction "1_1") (pintype "passive"))
      (node (ref "D9") (pin "1") (pinfunction "1_1") (pintype "passive"))
      (node (ref "EPD_C1") (pin "1") (pinfunction "1_1") (pintype "passive"))
      (node (ref "EPD_C10") (pin "1") (pinfunction "1_1") (pintype "passive"))
      (node (ref "EPD_C11") (pin "1") (pinfunction "1_1") (pintype "passive"))
      (node (ref "EPD_C12") (pin "1") (pinfunction "1_1") (pintype "passive"))
      (node (ref "EPD_C2") (pin "1") (pinfunction "1_1") (pintype "passive"))
      (node (ref "EPD_C5") (pin "1") (pinfunction "1_1") (pintype "passive"))
      (node (ref "EPD_C6") (pin "1") (pinfunction "1_1") (pintype "passive"))
      (node (ref "EPD_C7") (pin "1") (pinfunction "1_1") (pintype "passive"))
      (node (ref "EPD_C8") (pin "1") (pinfunction "1_1") (pintype "passive"))
      (node (ref "EPD_C9") (pin "1") (pinfunction "1_1") (pintype "passive"))
      (node (ref "IC1") (pin "3") (pinfunction "GND_3") (pintype "bidirectional"))
      (node (ref "IC4") (pin "2") (pinfunction "VSS_2") (pintype "bidirectional"))
      (node (ref "J1") (pin "17") (pinfunction "17_17") (pintype "bidirectional"))
      (node (ref "J1") (pin "8") (pinfunction "8_8") (pintype "bidirectional"))
      (node (ref "J1") (pin "MP1") (pinfunction "MP1_MP1") (pintype "bidirectional"))
      (node (ref "J1") (pin "MP2") (pinfunction "MP2_MP2") (pintype "bidirectional"))
      (node (ref "J2") (pin "A1") (pinfunction "A1_A1") (pintype "bidirectional"))
      (node (ref "J2") (pin "A12") (pinfunction "A12_A12") (pintype "bidirectional"))
      (node (ref "J2") (pin "B1") (pinfunction "B1_B1") (pintype "bidirectional"))
      (node (ref "J2") (pin "B12") (pinfunction "B12_B12") (pintype "bidirectional"))
      (node (ref "J2") (pin "MP1") (pinfunction "MP1_MP1") (pintype "bidirectional"))
      (node (ref "J2") (pin "MP2") (pinfunction "MP2_MP2") (pintype "bidirectional"))
      (node (ref "J2") (pin "MP3") (pinfunction "MP3_MP3") (pintype "bidirectional"))
      (node (ref "J2") (pin "MP4") (pinfunction "MP4_MP4") (pintype "bidirectional"))
      (node (ref "J3") (pin "1") (pinfunction "1_1") (pintype "power_in"))
      (node (ref "J4") (pin "G1") (pinfunction "GND_1_G1") (pintype "bidirectional"))
      (node (ref "J4") (pin "G2") (pinfunction "GND_2_G2") (pintype "bidirectional"))
      (node (ref "J4") (pin "G3") (pinfunction "GND_3_G3") (pintype "bidirectional"))
      (node (ref "J4") (pin "G4") (pinfunction "GND_4_G4") (pintype "bidirectional"))
      (node (ref "J4") (pin "P6") (pinfunction "VSS_P6") (pintype "bidirectional"))
      (node (ref "MCP73831") (pin "2") (pinfunction "VSS_2") (pintype "power_in"))
      (node (ref "R1_RWRUSB") (pin "1") (pinfunction "1_1") (pintype "passive"))
      (node (ref "R2") (pin "1") (pinfunction "1_1") (pintype "passive"))
      (node (ref "R2-USB") (pin "2") (pinfunction "2_2") (pintype "passive"))
      (node (ref "R2-USB1") (pin "1") (pinfunction "1_1") (pintype "passive"))
      (node (ref "R2_BAT") (pin "1") (pinfunction "1_1") (pintype "passive"))
      (node (ref "R4") (pin "1") (pinfunction "1_1") (pintype "passive"))
      (node (ref "RESET_BUTTON") (pin "1") (pinfunction "1_1") (pintype "passive"))
      (node (ref "RESET_BUTTON") (pin "2") (pinfunction "2_2") (pintype "passive"))
      (node (ref "SENSOR2") (pin "1") (pinfunction "GND_1") (pintype "power_in"))
      (node (ref "SENSOR2") (pin "5") (pinfunction "SDO_5") (pintype "bidirectional"))
      (node (ref "SENSOR2") (pin "7") (pinfunction "GND_7") (pintype "power_in"))
      (node (ref "SJ1") (pin "1") (pinfunction "1_1") (pintype "passive"))
      (node (ref "TP4") (pin "TP") (pinfunction "TP_TP") (pintype "input"))
      (node (ref "TP5") (pin "TP") (pinfunction "TP_TP") (pintype "input"))
      (node (ref "U1") (pin "4") (pinfunction "GND_4") (pintype "power_in"))
      (node (ref "U1") (pin "9") (pinfunction "EXP_9") (pintype "passive"))
      (node (ref "U2") (pin "1") (pinfunction "GND_1") (pintype "power_in"))
      (node (ref "U2") (pin "28") (pinfunction "GND_28") (pintype "power_in"))
      (node (ref "U2") (pin "29_1") (pinfunction "GND_29_1") (pintype "power_in"))
      (node (ref "U2") (pin "29_2") (pinfunction "GND_29_2") (pintype "power_in"))
      (node (ref "U2") (pin "29_3") (pinfunction "GND_29_3") (pintype "power_in"))
      (node (ref "U2") (pin "29_4") (pinfunction "GND_29_4") (pintype "power_in"))
      (node (ref "U2") (pin "29_5") (pinfunction "GND_29_5") (pintype "power_in"))
      (node (ref "U2") (pin "29_6") (pinfunction "GND_29_6") (pintype "power_in"))
      (node (ref "U2") (pin "29_7") (pinfunction "GND_29_7") (pintype "power_in"))
      (node (ref "U2") (pin "29_8") (pinfunction "GND_29_8") (pintype "power_in"))
      (node (ref "U2") (pin "29_9") (pinfunction "GND_29_9") (pintype "power_in"))
      (node (ref "U3") (pin "13") (pinfunction "GND_13") (pintype "power_in"))
      (node (ref "U4") (pin "1") (pinfunction "CTG_1") (pintype "power_in"))
      (node (ref "U4") (pin "4") (pinfunction "GND_4") (pintype "power_in"))
      (node (ref "U4") (pin "6") (pinfunction "QSTRT_6") (pintype "input"))
      (node (ref "U4") (pin "9") (pinfunction "EP_9") (pintype "power_in"))
    )
    (net (code "14") (name "GPIO8") (class "Default")
      (node (ref "R1") (pin "1") (pinfunction "1_1") (pintype "passive"))
      (node (ref "U2") (pin "10") (pinfunction "IO8_10") (pintype "bidirectional"))
    )
    (net (code "15") (name "I2C_PW") (class "Default")
      (node (ref "C1") (pin "1") (pinfunction "1_1") (pintype "passive"))
      (node (ref "C2") (pin "1") (pinfunction "1_1") (pintype "passive"))
      (node (ref "R1-PINH") (pin "2") (pinfunction "2_2") (pintype "passive"))
      (node (ref "R2-PINH") (pin "2") (pinfunction "2_2") (pintype "passive"))
      (node (ref "SENSOR2") (pin "6") (pinfunction "VDDIO_6") (pintype "power_in"))
      (node (ref "U2") (pin "17") (pinfunction "IO19_17") (pintype "bidirectional"))
    )
    (net (code "16") (name "INT_RTC") (class "Default")
      (node (ref "R1-PINH1") (pin "1") (pinfunction "1_1") (pintype "passive"))
      (node (ref "TP15") (pin "TP") (pinfunction "TP_TP") (pintype "input"))
      (node (ref "U2") (pin "8") (pinfunction "IO0_8") (pintype "bidirectional"))
      (node (ref "U3") (pin "3") (pinfunction "SQW/~{INT}_3") (pintype "output"))
    )
    (net (code "17") (name "IO{slash}BOOT") (class "Default")
      (node (ref "BOOT_BUTTON") (pin "1") (pinfunction "1_1") (pintype "passive"))
      (node (ref "BOOT_BUTTON") (pin "2") (pinfunction "2_2") (pintype "passive"))
      (node (ref "C6") (pin "1") (pinfunction "1_1") (pintype "passive"))
      (node (ref "R_BOOT") (pin "1") (pinfunction "1_1") (pintype "passive"))
      (node (ref "U2") (pin "15") (pinfunction "IO9_15") (pintype "bidirectional"))
    )
    (net (code "18") (name "IO{slash}CHANGE") (class "Default")
      (node (ref "C10") (pin "1") (pinfunction "1_1") (pintype "passive"))
      (node (ref "CHANGE_BUTTON") (pin "3") (pinfunction "3_3") (pintype "passive"))
      (node (ref "CHANGE_BUTTON") (pin "4") (pinfunction "4_4") (pintype "passive"))
      (node (ref "R_CHANGE") (pin "1") (pinfunction "1_1") (pintype "passive"))
      (node (ref "U2") (pin "23") (pinfunction "IO15_23") (pintype "bidirectional"))
    )
    (net (code "19") (name "MISO") (class "Default")
      (node (ref "D12") (pin "2") (pinfunction "2_2") (pintype "passive"))
      (node (ref "J4") (pin "P7") (pinfunction "DAT0_P7") (pintype "bidirectional"))
      (node (ref "R8") (pin "1") (pinfunction "1_1") (pintype "passive"))
      (node (ref "TP6") (pin "TP") (pinfunction "TP_TP") (pintype "input"))
      (node (ref "U1") (pin "2") (pinfunction "DO(IO1)_2") (pintype "bidirectional"))
      (node (ref "U2") (pin "27") (pinfunction "IO2_27") (pintype "bidirectional"))
    )
    (net (code "20") (name "MOSI") (class "Default")
      (node (ref "D11") (pin "2") (pinfunction "2_2") (pintype "passive"))
      (node (ref "J1") (pin "14") (pinfunction "14_14") (pintype "bidirectional"))
      (node (ref "J4") (pin "P3") (pinfunction "CMD_P3") (pintype "bidirectional"))
      (node (ref "R7") (pin "1") (pinfunction "1_1") (pintype "passive"))
      (node (ref "TP7") (pin "TP") (pinfunction "TP_TP") (pintype "input"))
      (node (ref "U1") (pin "5") (pinfunction "DI(IO0)_5") (pintype "bidirectional"))
      (node (ref "U2") (pin "7") (pinfunction "IO7_7") (pintype "bidirectional"))
    )
    (net (code "21") (name "Net-(CHG_LED-PadC)") (class "Default")
      (node (ref "CHG_LED") (pin "C") (pinfunction "C_C") (pintype "passive"))
      (node (ref "R1_BAT") (pin "1") (pinfunction "1_1") (pintype "passive"))
    )
    (net (code "22") (name "Net-(D2-ANODE)") (class "Default")
      (node (ref "D2") (pin "2") (pinfunction "ANODE_2") (pintype "bidirectional"))
      (node (ref "Q1") (pin "1") (pinfunction "G_1") (pintype "bidirectional"))
      (node (ref "R1_RWRUSB") (pin "2") (pinfunction "2_2") (pintype "passive"))
    )
    (net (code "23") (name "Net-(D2-CATHODE)") (class "Default")
      (node (ref "C1_BAT1") (pin "1") (pinfunction "1_1") (pintype "passive"))
      (node (ref "D2") (pin "1") (pinfunction "CATHODE_1") (pintype "bidirectional"))
      (node (ref "IC4") (pin "1") (pinfunction "VIN_1") (pintype "bidirectional"))
      (node (ref "IC4") (pin "3") (pinfunction "CE_3") (pintype "bidirectional"))
      (node (ref "Q1") (pin "2") (pinfunction "S_2") (pintype "bidirectional"))
    )
    (net (code "24") (name "Net-(D3-A)") (class "Default")
      (node (ref "C4") (pin "1") (pinfunction "1_1") (pintype "passive"))
      (node (ref "D3") (pin "2") (pinfunction "A_2") (pintype "bidirectional"))
      (node (ref "D4") (pin "1") (pinfunction "K_1") (pintype "bidirectional"))
    )
    (net (code "25") (name "Net-(D7-CATHODE)") (class "Default")
      (node (ref "D7") (pin "1") (pinfunction "CATHODE_1") (pintype "bidirectional"))
      (node (ref "R_CAPACITOR") (pin "1") (pinfunction "1_1") (pintype "passive"))
    )
    (net (code "26") (name "Net-(EPD_C1-Pad2)") (class "Default")
      (node (ref "EPD_C1") (pin "2") (pinfunction "2_2") (pintype "passive"))
      (node (ref "J1") (pin "4") (pinfunction "4_4") (pintype "bidirectional"))
    )
    (net (code "27") (name "Net-(EPD_C2-Pad2)") (class "Default")
      (node (ref "EPD_C2") (pin "2") (pinfunction "2_2") (pintype "passive"))
      (node (ref "J1") (pin "5") (pinfunction "5_5") (pintype "bidirectional"))
    )
    (net (code "28") (name "Net-(EPD_C6-Pad2)") (class "Default")
      (node (ref "EPD_C6") (pin "2") (pinfunction "2_2") (pintype "passive"))
      (node (ref "J1") (pin "18") (pinfunction "18_18") (pintype "bidirectional"))
    )
    (net (code "29") (name "Net-(EPD_C7-Pad2)") (class "Default")
      (node (ref "EPD_C7") (pin "2") (pinfunction "2_2") (pintype "passive"))
      (node (ref "J1") (pin "19") (pinfunction "19_19") (pintype "bidirectional"))
    )
    (net (code "30") (name "Net-(EPD_C8-Pad2)") (class "Default")
      (node (ref "EPD_C8") (pin "2") (pinfunction "2_2") (pintype "passive"))
      (node (ref "J1") (pin "20") (pinfunction "20_20") (pintype "bidirectional"))
    )
    (net (code "31") (name "Net-(EPD_C10-Pad2)") (class "Default")
      (node (ref "EPD_C10") (pin "2") (pinfunction "2_2") (pintype "passive"))
      (node (ref "J1") (pin "22") (pinfunction "22_22") (pintype "bidirectional"))
    )
    (net (code "32") (name "Net-(EPD_C12-Pad2)") (class "Default")
      (node (ref "EPD_C12") (pin "2") (pinfunction "2_2") (pintype "passive"))
      (node (ref "J1") (pin "24") (pinfunction "24_24") (pintype "bidirectional"))
    )
    (net (code "33") (name "Net-(IC1-CT)") (class "Default")
      (node (ref "C_DELAY") (pin "1") (pinfunction "1_1") (pintype "passive"))
      (node (ref "IC1") (pin "5") (pinfunction "CT_5") (pintype "bidirectional"))
    )
    (net (code "34") (name "Net-(J2-PadA5)") (class "Default")
      (node (ref "J2") (pin "A5") (pinfunction "A5_A5") (pintype "bidirectional"))
      (node (ref "R2-USB1") (pin "2") (pinfunction "2_2") (pintype "passive"))
    )
    (net (code "35") (name "Net-(J2-PadB5)") (class "Default")
      (node (ref "J2") (pin "B5") (pinfunction "B5_B5") (pintype "bidirectional"))
      (node (ref "R2-USB") (pin "1") (pinfunction "1_1") (pintype "passive"))
    )
    (net (code "36") (name "Net-(MCP73831-PROG)") (class "Default")
      (node (ref "MCP73831") (pin "5") (pinfunction "PROG_5") (pintype "input"))
      (node (ref "R2_BAT") (pin "2") (pinfunction "2_2") (pintype "passive"))
    )
    (net (code "37") (name "Net-(MCP73831-STAT)") (class "Default")
      (node (ref "MCP73831") (pin "1") (pinfunction "STAT_1") (pintype "output"))
      (node (ref "R1_BAT") (pin "2") (pinfunction "2_2") (pintype "passive"))
    )
    (net (code "38") (name "Net-(SENSOR2-CSB)") (class "Default")
      (node (ref "SENSOR2") (pin "2") (pinfunction "CSB_2") (pintype "input"))
      (node (ref "SENSOR2") (pin "8") (pinfunction "VDD_8") (pintype "power_in"))
    )
    (net (code "39") (name "PREVGH") (class "Default")
      (node (ref "D5") (pin "1") (pinfunction "K_1") (pintype "bidirectional"))
      (node (ref "EPD_C9") (pin "2") (pinfunction "2_2") (pintype "passive"))
      (node (ref "J1") (pin "21") (pinfunction "21_21") (pintype "bidirectional"))
    )
    (net (code "40") (name "PREVGL") (class "Default")
      (node (ref "D4") (pin "2") (pinfunction "A_2") (pintype "bidirectional"))
      (node (ref "EPD_C11") (pin "2") (pinfunction "2_2") (pintype "passive"))
      (node (ref "J1") (pin "23") (pinfunction "23_23") (pintype "bidirectional"))
    )
    (net (code "41") (name "RESE") (class "Default")
      (node (ref "J1") (pin "3") (pinfunction "3_3") (pintype "bidirectional"))
      (node (ref "Q3") (pin "2") (pinfunction "S_2") (pintype "bidirectional"))
      (node (ref "R3") (pin "2") (pinfunction "2_2") (pintype "passive"))
    )
    (net (code "42") (name "RESE'") (class "Default")
      (node (ref "R2") (pin "2") (pinfunction "2_2") (pintype "passive"))
      (node (ref "R3") (pin "1") (pinfunction "1_1") (pintype "passive"))
      (node (ref "SJ1") (pin "2") (pinfunction "2_2") (pintype "passive"))
    )
    (net (code "43") (name "RESET") (class "Default")
      (node (ref "C5") (pin "1") (pinfunction "1_1") (pintype "passive"))
      (node (ref "IC1") (pin "1") (pinfunction "VOUT_1") (pintype "bidirectional"))
      (node (ref "RESET_BUTTON") (pin "3") (pinfunction "3_3") (pintype "passive"))
      (node (ref "RESET_BUTTON") (pin "4") (pinfunction "4_4") (pintype "passive"))
      (node (ref "R_RESET") (pin "1") (pinfunction "1_1") (pintype "passive"))
      (node (ref "U2") (pin "3") (pinfunction "EN_3") (pintype "input"))
    )
    (net (code "44") (name "RTC_RST") (class "Default")
      (node (ref "U2") (pin "16") (pinfunction "IO18_16") (pintype "bidirectional"))
      (node (ref "U3") (pin "4") (pinfunction "~{RST}_4") (pintype "input"))
    )
    (net (code "45") (name "RX") (class "Default")
      (node (ref "TP2") (pin "TP") (pinfunction "TP_TP") (pintype "input"))
      (node (ref "U2") (pin "24") (pinfunction "RXD0/GPIO17_24") (pintype "bidirectional"))
    )
    (net (code "46") (name "SCK") (class "Default")
      (node (ref "D10") (pin "2") (pinfunction "2_2") (pintype "passive"))
      (node (ref "J1") (pin "13") (pinfunction "13_13") (pintype "bidirectional"))
      (node (ref "J4") (pin "P5") (pinfunction "CLK_P5") (pintype "bidirectional"))
      (node (ref "R6") (pin "1") (pinfunction "1_1") (pintype "passive"))
      (node (ref "TP8") (pin "TP") (pinfunction "TP_TP") (pintype "input"))
      (node (ref "U1") (pin "6") (pinfunction "CLK_6") (pintype "input"))
      (node (ref "U2") (pin "6") (pinfunction "IO6_6") (pintype "bidirectional"))
    )
    (net (code "47") (name "SCL") (class "Default")
      (node (ref "J3") (pin "4") (pinfunction "4_4") (pintype "passive"))
      (node (ref "R2-PINH") (pin "1") (pinfunction "1_1") (pintype "passive"))
      (node (ref "SENSOR2") (pin "4") (pinfunction "SCK_4") (pintype "input"))
      (node (ref "U2") (pin "20") (pinfunction "IO22_20") (pintype "bidirectional"))
      (node (ref "U3") (pin "16") (pinfunction "SCL_16") (pintype "input"))
      (node (ref "U4") (pin "7") (pinfunction "SCL_7") (pintype "input"))
    )
    (net (code "48") (name "SDA") (class "Default")
      (node (ref "J3") (pin "3") (pinfunction "3_3") (pintype "passive"))
      (node (ref "R1-PINH") (pin "1") (pinfunction "1_1") (pintype "passive"))
      (node (ref "SENSOR2") (pin "3") (pinfunction "SDI_3") (pintype "bidirectional"))
      (node (ref "U2") (pin "19") (pinfunction "IO21_19") (pintype "bidirectional"))
      (node (ref "U3") (pin "15") (pinfunction "SDA_15") (pintype "bidirectional"))
      (node (ref "U4") (pin "8") (pinfunction "SDA_8") (pintype "bidirectional"))
    )
    (net (code "49") (name "SRC") (class "Default")
      (node (ref "C4") (pin "2") (pinfunction "2_2") (pintype "passive"))
      (node (ref "D5") (pin "2") (pinfunction "A_2") (pintype "bidirectional"))
      (node (ref "L1") (pin "1") (pinfunction "1_1") (pintype "passive"))
      (node (ref "Q3") (pin "3") (pinfunction "D_3") (pintype "bidirectional"))
    )
    (net (code "50") (name "SS_SD") (class "Default")
      (node (ref "D8") (pin "2") (pinfunction "2_2") (pintype "passive"))
      (node (ref "J4") (pin "P2") (pinfunction "CD/DAT3_P2") (pintype "bidirectional"))
      (node (ref "R10") (pin "1") (pinfunction "1_1") (pintype "passive"))
      (node (ref "U2") (pin "4") (pinfunction "IO4_4") (pintype "bidirectional"))
    )
    (net (code "51") (name "TX") (class "Default")
      (node (ref "TP1") (pin "TP") (pinfunction "TP_TP") (pintype "input"))
      (node (ref "U2") (pin "25") (pinfunction "TXD0/GPIO16_25") (pintype "bidirectional"))
    )
    (net (code "52") (name "USB_D+") (class "Default")
      (node (ref "D1") (pin "1") (pinfunction "I/O1_1_1") (pintype "bidirectional"))
      (node (ref "U2") (pin "14") (pinfunction "IO13_14") (pintype "bidirectional"))
    )
    (net (code "53") (name "USB_D-") (class "Default")
      (node (ref "D1") (pin "3") (pinfunction "I/O2_1_3") (pintype "bidirectional"))
      (node (ref "U2") (pin "13") (pinfunction "IO12_13") (pintype "bidirectional"))
    )
    (net (code "54") (name "VBAT") (class "Default")
      (node (ref "C2_BAT") (pin "1") (pinfunction "1_1") (pintype "passive"))
      (node (ref "MCP73831") (pin "3") (pinfunction "VBAT_3") (pintype "power_in"))
      (node (ref "Q1") (pin "3") (pinfunction "D_3") (pintype "bidirectional"))
      (node (ref "TP3") (pin "TP") (pinfunction "TP_TP") (pintype "input"))
      (node (ref "U4") (pin "2") (pinfunction "CELL_2") (pintype "power_in"))
      (node (ref "U4") (pin "3") (pinfunction "VDD_3") (pintype "power_in"))
    )
    (net (code "55") (name "VBUS") (class "Default")
      (node (ref "C1_BAT") (pin "1") (pinfunction "1_1") (pintype "passive"))
      (node (ref "C4_USB") (pin "1") (pinfunction "1_1") (pintype "passive"))
      (node (ref "C5_USB") (pin "1") (pinfunction "1_1") (pintype "passive"))
      (node (ref "CHG_LED") (pin "A") (pinfunction "A_A") (pintype "passive"))
      (node (ref "D1") (pin "5") (pinfunction "VBUS_5") (pintype "bidirectional"))
      (node (ref "MCP73831") (pin "4") (pinfunction "VIN_4") (pintype "power_in"))
      (node (ref "PFMF.050.1") (pin "2") (pinfunction "2_2") (pintype "passive"))
      (node (ref "TP14") (pin "TP") (pinfunction "TP_TP") (pintype "input"))
    )
    (net (code "56") (name "VRTC") (class "Default")
      (node (ref "C10_SUPERCAP") (pin "2") (pinfunction "2_2") (pintype "passive"))
      (node (ref "C8") (pin "1") (pinfunction "1_1") (pintype "passive"))
      (node (ref "R_CAPACITOR") (pin "2") (pinfunction "2_2") (pintype "passive"))
      (node (ref "U3") (pin "14") (pinfunction "VBAT_14") (pintype "power_in"))
    )
    (net (code "57") (name "VUSB") (class "Default")
      (node (ref "J2") (pin "A4") (pinfunction "A4_A4") (pintype "bidirectional"))
      (node (ref "J2") (pin "A9") (pinfunction "A9_A9") (pintype "bidirectional"))
      (node (ref "J2") (pin "B4") (pinfunction "B4_B4") (pintype "bidirectional"))
      (node (ref "J2") (pin "B9") (pinfunction "B9_B9") (pintype "bidirectional"))
      (node (ref "PFMF.050.1") (pin "1") (pinfunction "1_1") (pintype "passive"))
    )
    (net (code "58") (name "unconnected-(IC1-NC-Pad4)") (class "Default")
      (node (ref "IC1") (pin "4") (pinfunction "NC_4") (pintype "no_connect"))
    )
    (net (code "59") (name "unconnected-(IC4-NC-Pad4)") (class "Default")
      (node (ref "IC4") (pin "4") (pinfunction "NC_4") (pintype "no_connect"))
    )
    (net (code "60") (name "unconnected-(J1-Pad1)") (class "Default")
      (node (ref "J1") (pin "1") (pinfunction "1_1") (pintype "bidirectional"))
    )
    (net (code "61") (name "unconnected-(J1-Pad6)") (class "Default")
      (node (ref "J1") (pin "6") (pinfunction "6_6") (pintype "bidirectional"))
    )
    (net (code "62") (name "unconnected-(J1-Pad7)") (class "Default")
      (node (ref "J1") (pin "7") (pinfunction "7_7") (pintype "bidirectional"))
    )
    (net (code "63") (name "unconnected-(J2-PadA8)") (class "Default")
      (node (ref "J2") (pin "A8") (pinfunction "A8_A8") (pintype "bidirectional"))
    )
    (net (code "64") (name "unconnected-(J2-PadB8)") (class "Default")
      (node (ref "J2") (pin "B8") (pinfunction "B8_B8") (pintype "bidirectional"))
    )
    (net (code "65") (name "unconnected-(J4-DAT1-PadP8)") (class "Default")
      (node (ref "J4") (pin "P8") (pinfunction "DAT1_P8") (pintype "bidirectional"))
    )
    (net (code "66") (name "unconnected-(J4-DAT2-PadP1)") (class "Default")
      (node (ref "J4") (pin "P1") (pinfunction "DAT2_P1") (pintype "bidirectional"))
    )
    (net (code "67") (name "unconnected-(J4-DETECTION_1-PadS1)") (class "Default")
      (node (ref "J4") (pin "S1") (pinfunction "DETECTION_1_S1") (pintype "bidirectional"))
    )
    (net (code "68") (name "unconnected-(J4-DETECTION_2-PadS2)") (class "Default")
      (node (ref "J4") (pin "S2") (pinfunction "DETECTION_2_S2") (pintype "bidirectional"))
    )
    (net (code "69") (name "unconnected-(U2-NC-Pad22)") (class "Default")
      (node (ref "U2") (pin "22") (pinfunction "NC_22") (pintype "no_connect"))
    )
    (net (code "70") (name "unconnected-(U4-~{ALERT}-Pad5)") (class "Default")
      (node (ref "U4") (pin "5") (pinfunction "~{ALERT}_5") (pintype "output"))
    )
  )
)
